# Pressure.net
KiCad netlist of a schematic drawn in EAGLE
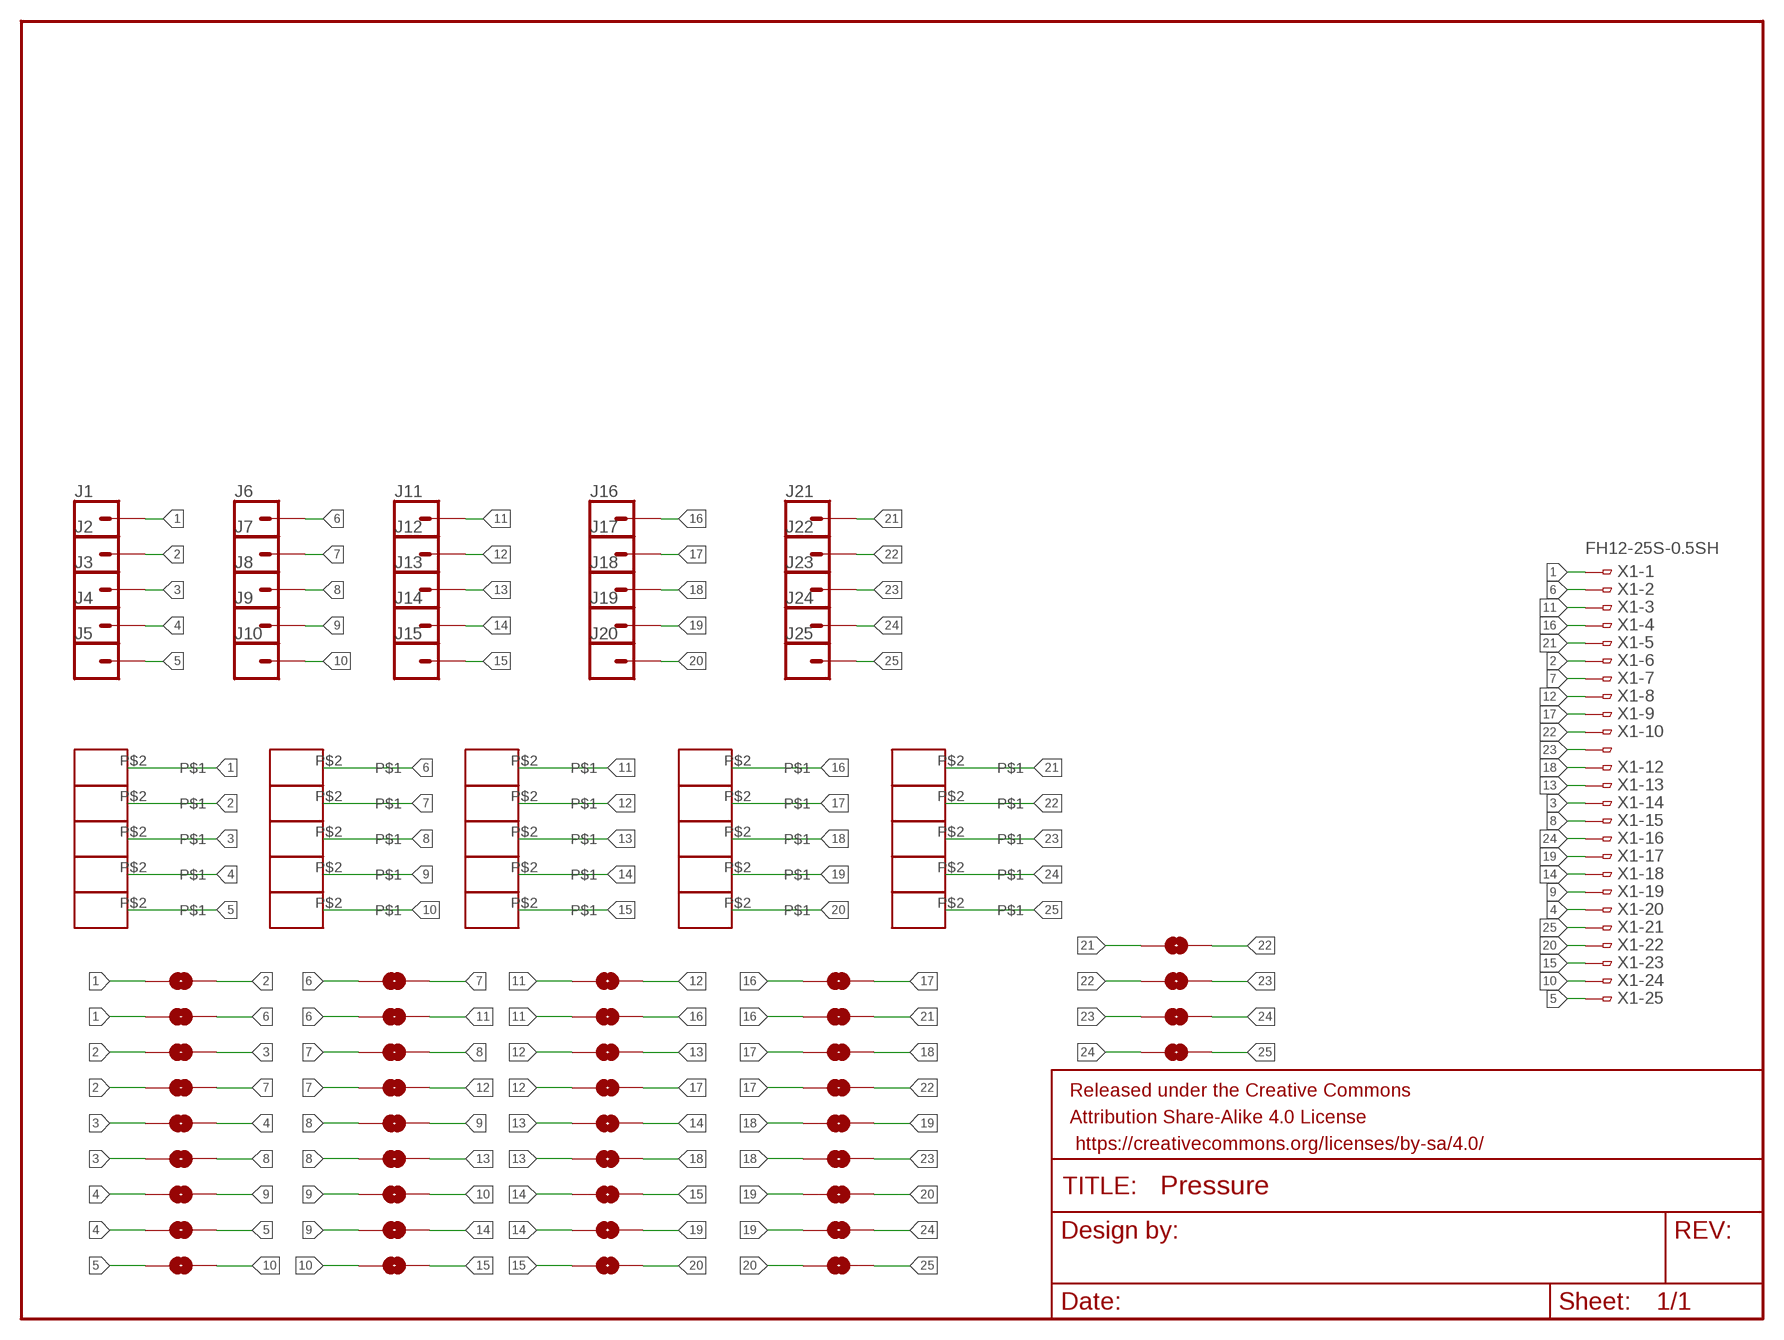
[diagram p0: schematic, sheet 1]

(export (version "E")
  (design (tool "Eeschema 10.0.6"))
  (components
    (comp (ref "FRAME1")
      (value "FRAME-LETTERNO_PACKAGE")
      (footprint "eagle-import:DUMMY")
      (fields (field (name "DESIGNER") "Nobody"))
      (libsource (lib "eagle-import") (part "FRAME-LETTERNO_PACKAGE"))
    )
    (comp (ref "J1")
      (value "CONN_01PTH_NO_SILK_YES_STOP")
      (footprint "eagle-import:1X01_NO_SILK")
      (libsource (lib "eagle-import") (part "CONN_01PTH_NO_SILK_YES_STOP"))
    )
    (comp (ref "J2")
      (value "CONN_01PTH_NO_SILK_YES_STOP")
      (footprint "eagle-import:1X01_NO_SILK")
      (libsource (lib "eagle-import") (part "CONN_01PTH_NO_SILK_YES_STOP"))
    )
    (comp (ref "J3")
      (value "CONN_01PTH_NO_SILK_YES_STOP")
      (footprint "eagle-import:1X01_NO_SILK")
      (libsource (lib "eagle-import") (part "CONN_01PTH_NO_SILK_YES_STOP"))
    )
    (comp (ref "J4")
      (value "CONN_01PTH_NO_SILK_YES_STOP")
      (footprint "eagle-import:1X01_NO_SILK")
      (libsource (lib "eagle-import") (part "CONN_01PTH_NO_SILK_YES_STOP"))
    )
    (comp (ref "J5")
      (value "CONN_01PTH_NO_SILK_YES_STOP")
      (footprint "eagle-import:1X01_NO_SILK")
      (libsource (lib "eagle-import") (part "CONN_01PTH_NO_SILK_YES_STOP"))
    )
    (comp (ref "J6")
      (value "CONN_01PTH_NO_SILK_YES_STOP")
      (footprint "eagle-import:1X01_NO_SILK")
      (libsource (lib "eagle-import") (part "CONN_01PTH_NO_SILK_YES_STOP"))
    )
    (comp (ref "J7")
      (value "CONN_01PTH_NO_SILK_YES_STOP")
      (footprint "eagle-import:1X01_NO_SILK")
      (libsource (lib "eagle-import") (part "CONN_01PTH_NO_SILK_YES_STOP"))
    )
    (comp (ref "J8")
      (value "CONN_01PTH_NO_SILK_YES_STOP")
      (footprint "eagle-import:1X01_NO_SILK")
      (libsource (lib "eagle-import") (part "CONN_01PTH_NO_SILK_YES_STOP"))
    )
    (comp (ref "J9")
      (value "CONN_01PTH_NO_SILK_YES_STOP")
      (footprint "eagle-import:1X01_NO_SILK")
      (libsource (lib "eagle-import") (part "CONN_01PTH_NO_SILK_YES_STOP"))
    )
    (comp (ref "J10")
      (value "CONN_01PTH_NO_SILK_YES_STOP")
      (footprint "eagle-import:1X01_NO_SILK")
      (libsource (lib "eagle-import") (part "CONN_01PTH_NO_SILK_YES_STOP"))
    )
    (comp (ref "J11")
      (value "CONN_01PTH_NO_SILK_YES_STOP")
      (footprint "eagle-import:1X01_NO_SILK")
      (libsource (lib "eagle-import") (part "CONN_01PTH_NO_SILK_YES_STOP"))
    )
    (comp (ref "J12")
      (value "CONN_01PTH_NO_SILK_YES_STOP")
      (footprint "eagle-import:1X01_NO_SILK")
      (libsource (lib "eagle-import") (part "CONN_01PTH_NO_SILK_YES_STOP"))
    )
    (comp (ref "J13")
      (value "CONN_01PTH_NO_SILK_YES_STOP")
      (footprint "eagle-import:1X01_NO_SILK")
      (libsource (lib "eagle-import") (part "CONN_01PTH_NO_SILK_YES_STOP"))
    )
    (comp (ref "J14")
      (value "CONN_01PTH_NO_SILK_YES_STOP")
      (footprint "eagle-import:1X01_NO_SILK")
      (libsource (lib "eagle-import") (part "CONN_01PTH_NO_SILK_YES_STOP"))
    )
    (comp (ref "J15")
      (value "CONN_01PTH_NO_SILK_YES_STOP")
      (footprint "eagle-import:1X01_NO_SILK")
      (libsource (lib "eagle-import") (part "CONN_01PTH_NO_SILK_YES_STOP"))
    )
    (comp (ref "J16")
      (value "CONN_01PTH_NO_SILK_YES_STOP")
      (footprint "eagle-import:1X01_NO_SILK")
      (libsource (lib "eagle-import") (part "CONN_01PTH_NO_SILK_YES_STOP"))
    )
    (comp (ref "J17")
      (value "CONN_01PTH_NO_SILK_YES_STOP")
      (footprint "eagle-import:1X01_NO_SILK")
      (libsource (lib "eagle-import") (part "CONN_01PTH_NO_SILK_YES_STOP"))
    )
    (comp (ref "J18")
      (value "CONN_01PTH_NO_SILK_YES_STOP")
      (footprint "eagle-import:1X01_NO_SILK")
      (libsource (lib "eagle-import") (part "CONN_01PTH_NO_SILK_YES_STOP"))
    )
    (comp (ref "J19")
      (value "CONN_01PTH_NO_SILK_YES_STOP")
      (footprint "eagle-import:1X01_NO_SILK")
      (libsource (lib "eagle-import") (part "CONN_01PTH_NO_SILK_YES_STOP"))
    )
    (comp (ref "J20")
      (value "CONN_01PTH_NO_SILK_YES_STOP")
      (footprint "eagle-import:1X01_NO_SILK")
      (libsource (lib "eagle-import") (part "CONN_01PTH_NO_SILK_YES_STOP"))
    )
    (comp (ref "J21")
      (value "CONN_01PTH_NO_SILK_YES_STOP")
      (footprint "eagle-import:1X01_NO_SILK")
      (libsource (lib "eagle-import") (part "CONN_01PTH_NO_SILK_YES_STOP"))
    )
    (comp (ref "J22")
      (value "CONN_01PTH_NO_SILK_YES_STOP")
      (footprint "eagle-import:1X01_NO_SILK")
      (libsource (lib "eagle-import") (part "CONN_01PTH_NO_SILK_YES_STOP"))
    )
    (comp (ref "J23")
      (value "CONN_01PTH_NO_SILK_YES_STOP")
      (footprint "eagle-import:1X01_NO_SILK")
      (libsource (lib "eagle-import") (part "CONN_01PTH_NO_SILK_YES_STOP"))
    )
    (comp (ref "J24")
      (value "CONN_01PTH_NO_SILK_YES_STOP")
      (footprint "eagle-import:1X01_NO_SILK")
      (libsource (lib "eagle-import") (part "CONN_01PTH_NO_SILK_YES_STOP"))
    )
    (comp (ref "J25")
      (value "CONN_01PTH_NO_SILK_YES_STOP")
      (footprint "eagle-import:1X01_NO_SILK")
      (libsource (lib "eagle-import") (part "CONN_01PTH_NO_SILK_YES_STOP"))
    )
    (comp (ref "JP1")
      (value "JUMPER-SMT_2_NO_NO-SILK")
      (footprint "eagle-import:SMT-JUMPER_2_NO_NO-SILK")
      (libsource (lib "eagle-import") (part "JUMPER-SMT_2_NO_NO-SILK"))
    )
    (comp (ref "JP2")
      (value "JUMPER-SMT_2_NO_NO-SILK")
      (footprint "eagle-import:SMT-JUMPER_2_NO_NO-SILK")
      (libsource (lib "eagle-import") (part "JUMPER-SMT_2_NO_NO-SILK"))
    )
    (comp (ref "JP3")
      (value "JUMPER-SMT_2_NO_NO-SILK")
      (footprint "eagle-import:SMT-JUMPER_2_NO_NO-SILK")
      (libsource (lib "eagle-import") (part "JUMPER-SMT_2_NO_NO-SILK"))
    )
    (comp (ref "JP4")
      (value "JUMPER-SMT_2_NO_NO-SILK")
      (footprint "eagle-import:SMT-JUMPER_2_NO_NO-SILK")
      (libsource (lib "eagle-import") (part "JUMPER-SMT_2_NO_NO-SILK"))
    )
    (comp (ref "JP5")
      (value "JUMPER-SMT_2_NO_NO-SILK")
      (footprint "eagle-import:SMT-JUMPER_2_NO_NO-SILK")
      (libsource (lib "eagle-import") (part "JUMPER-SMT_2_NO_NO-SILK"))
    )
    (comp (ref "JP6")
      (value "JUMPER-SMT_2_NO_NO-SILK")
      (footprint "eagle-import:SMT-JUMPER_2_NO_NO-SILK")
      (libsource (lib "eagle-import") (part "JUMPER-SMT_2_NO_NO-SILK"))
    )
    (comp (ref "JP7")
      (value "JUMPER-SMT_2_NO_NO-SILK")
      (footprint "eagle-import:SMT-JUMPER_2_NO_NO-SILK")
      (libsource (lib "eagle-import") (part "JUMPER-SMT_2_NO_NO-SILK"))
    )
    (comp (ref "JP8")
      (value "JUMPER-SMT_2_NO_NO-SILK")
      (footprint "eagle-import:SMT-JUMPER_2_NO_NO-SILK")
      (libsource (lib "eagle-import") (part "JUMPER-SMT_2_NO_NO-SILK"))
    )
    (comp (ref "JP9")
      (value "JUMPER-SMT_2_NO_NO-SILK")
      (footprint "eagle-import:SMT-JUMPER_2_NO_NO-SILK")
      (libsource (lib "eagle-import") (part "JUMPER-SMT_2_NO_NO-SILK"))
    )
    (comp (ref "JP10")
      (value "JUMPER-SMT_2_NO_NO-SILK")
      (footprint "eagle-import:SMT-JUMPER_2_NO_NO-SILK")
      (libsource (lib "eagle-import") (part "JUMPER-SMT_2_NO_NO-SILK"))
    )
    (comp (ref "JP11")
      (value "JUMPER-SMT_2_NO_NO-SILK")
      (footprint "eagle-import:SMT-JUMPER_2_NO_NO-SILK")
      (libsource (lib "eagle-import") (part "JUMPER-SMT_2_NO_NO-SILK"))
    )
    (comp (ref "JP12")
      (value "JUMPER-SMT_2_NO_NO-SILK")
      (footprint "eagle-import:SMT-JUMPER_2_NO_NO-SILK")
      (libsource (lib "eagle-import") (part "JUMPER-SMT_2_NO_NO-SILK"))
    )
    (comp (ref "JP13")
      (value "JUMPER-SMT_2_NO_NO-SILK")
      (footprint "eagle-import:SMT-JUMPER_2_NO_NO-SILK")
      (libsource (lib "eagle-import") (part "JUMPER-SMT_2_NO_NO-SILK"))
    )
    (comp (ref "JP14")
      (value "JUMPER-SMT_2_NO_NO-SILK")
      (footprint "eagle-import:SMT-JUMPER_2_NO_NO-SILK")
      (libsource (lib "eagle-import") (part "JUMPER-SMT_2_NO_NO-SILK"))
    )
    (comp (ref "JP15")
      (value "JUMPER-SMT_2_NO_NO-SILK")
      (footprint "eagle-import:SMT-JUMPER_2_NO_NO-SILK")
      (libsource (lib "eagle-import") (part "JUMPER-SMT_2_NO_NO-SILK"))
    )
    (comp (ref "JP16")
      (value "JUMPER-SMT_2_NO_NO-SILK")
      (footprint "eagle-import:SMT-JUMPER_2_NO_NO-SILK")
      (libsource (lib "eagle-import") (part "JUMPER-SMT_2_NO_NO-SILK"))
    )
    (comp (ref "JP17")
      (value "JUMPER-SMT_2_NO_NO-SILK")
      (footprint "eagle-import:SMT-JUMPER_2_NO_NO-SILK")
      (libsource (lib "eagle-import") (part "JUMPER-SMT_2_NO_NO-SILK"))
    )
    (comp (ref "JP18")
      (value "JUMPER-SMT_2_NO_NO-SILK")
      (footprint "eagle-import:SMT-JUMPER_2_NO_NO-SILK")
      (libsource (lib "eagle-import") (part "JUMPER-SMT_2_NO_NO-SILK"))
    )
    (comp (ref "JP19")
      (value "JUMPER-SMT_2_NO_NO-SILK")
      (footprint "eagle-import:SMT-JUMPER_2_NO_NO-SILK")
      (libsource (lib "eagle-import") (part "JUMPER-SMT_2_NO_NO-SILK"))
    )
    (comp (ref "JP20")
      (value "JUMPER-SMT_2_NO_NO-SILK")
      (footprint "eagle-import:SMT-JUMPER_2_NO_NO-SILK")
      (libsource (lib "eagle-import") (part "JUMPER-SMT_2_NO_NO-SILK"))
    )
    (comp (ref "JP21")
      (value "JUMPER-SMT_2_NO_NO-SILK")
      (footprint "eagle-import:SMT-JUMPER_2_NO_NO-SILK")
      (libsource (lib "eagle-import") (part "JUMPER-SMT_2_NO_NO-SILK"))
    )
    (comp (ref "JP22")
      (value "JUMPER-SMT_2_NO_NO-SILK")
      (footprint "eagle-import:SMT-JUMPER_2_NO_NO-SILK")
      (libsource (lib "eagle-import") (part "JUMPER-SMT_2_NO_NO-SILK"))
    )
    (comp (ref "JP23")
      (value "JUMPER-SMT_2_NO_NO-SILK")
      (footprint "eagle-import:SMT-JUMPER_2_NO_NO-SILK")
      (libsource (lib "eagle-import") (part "JUMPER-SMT_2_NO_NO-SILK"))
    )
    (comp (ref "JP24")
      (value "JUMPER-SMT_2_NO_NO-SILK")
      (footprint "eagle-import:SMT-JUMPER_2_NO_NO-SILK")
      (libsource (lib "eagle-import") (part "JUMPER-SMT_2_NO_NO-SILK"))
    )
    (comp (ref "JP25")
      (value "JUMPER-SMT_2_NO_NO-SILK")
      (footprint "eagle-import:SMT-JUMPER_2_NO_NO-SILK")
      (libsource (lib "eagle-import") (part "JUMPER-SMT_2_NO_NO-SILK"))
    )
    (comp (ref "JP26")
      (value "JUMPER-SMT_2_NO_NO-SILK")
      (footprint "eagle-import:SMT-JUMPER_2_NO_NO-SILK")
      (libsource (lib "eagle-import") (part "JUMPER-SMT_2_NO_NO-SILK"))
    )
    (comp (ref "JP27")
      (value "JUMPER-SMT_2_NO_NO-SILK")
      (footprint "eagle-import:SMT-JUMPER_2_NO_NO-SILK")
      (libsource (lib "eagle-import") (part "JUMPER-SMT_2_NO_NO-SILK"))
    )
    (comp (ref "JP28")
      (value "JUMPER-SMT_2_NO_NO-SILK")
      (footprint "eagle-import:SMT-JUMPER_2_NO_NO-SILK")
      (libsource (lib "eagle-import") (part "JUMPER-SMT_2_NO_NO-SILK"))
    )
    (comp (ref "JP29")
      (value "JUMPER-SMT_2_NO_NO-SILK")
      (footprint "eagle-import:SMT-JUMPER_2_NO_NO-SILK")
      (libsource (lib "eagle-import") (part "JUMPER-SMT_2_NO_NO-SILK"))
    )
    (comp (ref "JP30")
      (value "JUMPER-SMT_2_NO_NO-SILK")
      (footprint "eagle-import:SMT-JUMPER_2_NO_NO-SILK")
      (libsource (lib "eagle-import") (part "JUMPER-SMT_2_NO_NO-SILK"))
    )
    (comp (ref "JP31")
      (value "JUMPER-SMT_2_NO_NO-SILK")
      (footprint "eagle-import:SMT-JUMPER_2_NO_NO-SILK")
      (libsource (lib "eagle-import") (part "JUMPER-SMT_2_NO_NO-SILK"))
    )
    (comp (ref "JP32")
      (value "JUMPER-SMT_2_NO_NO-SILK")
      (footprint "eagle-import:SMT-JUMPER_2_NO_NO-SILK")
      (libsource (lib "eagle-import") (part "JUMPER-SMT_2_NO_NO-SILK"))
    )
    (comp (ref "JP33")
      (value "JUMPER-SMT_2_NO_NO-SILK")
      (footprint "eagle-import:SMT-JUMPER_2_NO_NO-SILK")
      (libsource (lib "eagle-import") (part "JUMPER-SMT_2_NO_NO-SILK"))
    )
    (comp (ref "JP34")
      (value "JUMPER-SMT_2_NO_NO-SILK")
      (footprint "eagle-import:SMT-JUMPER_2_NO_NO-SILK")
      (libsource (lib "eagle-import") (part "JUMPER-SMT_2_NO_NO-SILK"))
    )
    (comp (ref "JP35")
      (value "JUMPER-SMT_2_NO_NO-SILK")
      (footprint "eagle-import:SMT-JUMPER_2_NO_NO-SILK")
      (libsource (lib "eagle-import") (part "JUMPER-SMT_2_NO_NO-SILK"))
    )
    (comp (ref "JP36")
      (value "JUMPER-SMT_2_NO_NO-SILK")
      (footprint "eagle-import:SMT-JUMPER_2_NO_NO-SILK")
      (libsource (lib "eagle-import") (part "JUMPER-SMT_2_NO_NO-SILK"))
    )
    (comp (ref "JP37")
      (value "JUMPER-SMT_2_NO_NO-SILK")
      (footprint "eagle-import:SMT-JUMPER_2_NO_NO-SILK")
      (libsource (lib "eagle-import") (part "JUMPER-SMT_2_NO_NO-SILK"))
    )
    (comp (ref "JP38")
      (value "JUMPER-SMT_2_NO_NO-SILK")
      (footprint "eagle-import:SMT-JUMPER_2_NO_NO-SILK")
      (libsource (lib "eagle-import") (part "JUMPER-SMT_2_NO_NO-SILK"))
    )
    (comp (ref "JP39")
      (value "JUMPER-SMT_2_NO_NO-SILK")
      (footprint "eagle-import:SMT-JUMPER_2_NO_NO-SILK")
      (libsource (lib "eagle-import") (part "JUMPER-SMT_2_NO_NO-SILK"))
    )
    (comp (ref "JP40")
      (value "JUMPER-SMT_2_NO_NO-SILK")
      (footprint "eagle-import:SMT-JUMPER_2_NO_NO-SILK")
      (libsource (lib "eagle-import") (part "JUMPER-SMT_2_NO_NO-SILK"))
    )
    (comp (ref "U$1")
      (value "250MIL_1X1")
      (footprint "eagle-import:250MIL_1X1")
      (libsource (lib "eagle-import") (part "250MIL_1X1"))
    )
    (comp (ref "U$2")
      (value "250MIL_1X1")
      (footprint "eagle-import:250MIL_1X1")
      (libsource (lib "eagle-import") (part "250MIL_1X1"))
    )
    (comp (ref "U$3")
      (value "250MIL_1X1")
      (footprint "eagle-import:250MIL_1X1")
      (libsource (lib "eagle-import") (part "250MIL_1X1"))
    )
    (comp (ref "U$4")
      (value "250MIL_1X1")
      (footprint "eagle-import:250MIL_1X1")
      (libsource (lib "eagle-import") (part "250MIL_1X1"))
    )
    (comp (ref "U$5")
      (value "250MIL_1X1")
      (footprint "eagle-import:250MIL_1X1")
      (libsource (lib "eagle-import") (part "250MIL_1X1"))
    )
    (comp (ref "U$6")
      (value "250MIL_1X1")
      (footprint "eagle-import:250MIL_1X1")
      (libsource (lib "eagle-import") (part "250MIL_1X1"))
    )
    (comp (ref "U$7")
      (value "250MIL_1X1")
      (footprint "eagle-import:250MIL_1X1")
      (libsource (lib "eagle-import") (part "250MIL_1X1"))
    )
    (comp (ref "U$8")
      (value "250MIL_1X1")
      (footprint "eagle-import:250MIL_1X1")
      (libsource (lib "eagle-import") (part "250MIL_1X1"))
    )
    (comp (ref "U$9")
      (value "250MIL_1X1")
      (footprint "eagle-import:250MIL_1X1")
      (libsource (lib "eagle-import") (part "250MIL_1X1"))
    )
    (comp (ref "U$10")
      (value "250MIL_1X1")
      (footprint "eagle-import:250MIL_1X1")
      (libsource (lib "eagle-import") (part "250MIL_1X1"))
    )
    (comp (ref "U$11")
      (value "250MIL_1X1")
      (footprint "eagle-import:250MIL_1X1")
      (libsource (lib "eagle-import") (part "250MIL_1X1"))
    )
    (comp (ref "U$12")
      (value "250MIL_1X1")
      (footprint "eagle-import:250MIL_1X1")
      (libsource (lib "eagle-import") (part "250MIL_1X1"))
    )
    (comp (ref "U$13")
      (value "250MIL_1X1")
      (footprint "eagle-import:250MIL_1X1")
      (libsource (lib "eagle-import") (part "250MIL_1X1"))
    )
    (comp (ref "U$14")
      (value "250MIL_1X1")
      (footprint "eagle-import:250MIL_1X1")
      (libsource (lib "eagle-import") (part "250MIL_1X1"))
    )
    (comp (ref "U$15")
      (value "250MIL_1X1")
      (footprint "eagle-import:250MIL_1X1")
      (libsource (lib "eagle-import") (part "250MIL_1X1"))
    )
    (comp (ref "U$16")
      (value "250MIL_1X1")
      (footprint "eagle-import:250MIL_1X1")
      (libsource (lib "eagle-import") (part "250MIL_1X1"))
    )
    (comp (ref "U$17")
      (value "250MIL_1X1")
      (footprint "eagle-import:250MIL_1X1")
      (libsource (lib "eagle-import") (part "250MIL_1X1"))
    )
    (comp (ref "U$18")
      (value "250MIL_1X1")
      (footprint "eagle-import:250MIL_1X1")
      (libsource (lib "eagle-import") (part "250MIL_1X1"))
    )
    (comp (ref "U$19")
      (value "250MIL_1X1")
      (footprint "eagle-import:250MIL_1X1")
      (libsource (lib "eagle-import") (part "250MIL_1X1"))
    )
    (comp (ref "U$20")
      (value "250MIL_1X1")
      (footprint "eagle-import:250MIL_1X1")
      (libsource (lib "eagle-import") (part "250MIL_1X1"))
    )
    (comp (ref "U$21")
      (value "250MIL_1X1")
      (footprint "eagle-import:250MIL_1X1")
      (libsource (lib "eagle-import") (part "250MIL_1X1"))
    )
    (comp (ref "U$22")
      (value "250MIL_1X1")
      (footprint "eagle-import:250MIL_1X1")
      (libsource (lib "eagle-import") (part "250MIL_1X1"))
    )
    (comp (ref "U$23")
      (value "250MIL_1X1")
      (footprint "eagle-import:250MIL_1X1")
      (libsource (lib "eagle-import") (part "250MIL_1X1"))
    )
    (comp (ref "U$24")
      (value "250MIL_1X1")
      (footprint "eagle-import:250MIL_1X1")
      (libsource (lib "eagle-import") (part "250MIL_1X1"))
    )
    (comp (ref "U$25")
      (value "250MIL_1X1")
      (footprint "eagle-import:250MIL_1X1")
      (libsource (lib "eagle-import") (part "250MIL_1X1"))
    )
    (comp (ref "X1")
      (value "FH12-25S-0.5SH")
      (footprint "eagle-import:FH12-25S-0.5SH")
      (libsource (lib "eagle-import") (part "FH12-25S-0.5SH"))
    )
  )
  (nets
    (net (code "1") (name "1") (class "Default")
      (node (ref "J1") (pin "1") (pinfunction "1_1") (pintype "passive"))
      (node (ref "JP1") (pin "1") (pinfunction "1_1") (pintype "passive"))
      (node (ref "JP2") (pin "1") (pinfunction "1_1") (pintype "passive"))
      (node (ref "U$1") (pin "P$2") (pinfunction "P$1_P$2") (pintype "bidirectional"))
      (node (ref "X1") (pin "1") (pinfunction "1_1") (pintype "passive"))
    )
    (net (code "2") (name "2") (class "Default")
      (node (ref "J2") (pin "1") (pinfunction "1_1") (pintype "passive"))
      (node (ref "JP1") (pin "2") (pinfunction "2_2") (pintype "passive"))
      (node (ref "JP3") (pin "1") (pinfunction "1_1") (pintype "passive"))
      (node (ref "JP4") (pin "1") (pinfunction "1_1") (pintype "passive"))
      (node (ref "U$2") (pin "P$2") (pinfunction "P$1_P$2") (pintype "bidirectional"))
      (node (ref "X1") (pin "6") (pinfunction "1_6") (pintype "passive"))
    )
    (net (code "3") (name "3") (class "Default")
      (node (ref "J3") (pin "1") (pinfunction "1_1") (pintype "passive"))
      (node (ref "JP3") (pin "2") (pinfunction "2_2") (pintype "passive"))
      (node (ref "JP5") (pin "1") (pinfunction "1_1") (pintype "passive"))
      (node (ref "JP6") (pin "1") (pinfunction "1_1") (pintype "passive"))
      (node (ref "U$3") (pin "P$2") (pinfunction "P$1_P$2") (pintype "bidirectional"))
      (node (ref "X1") (pin "14") (pinfunction "1_14") (pintype "passive"))
    )
    (net (code "4") (name "4") (class "Default")
      (node (ref "J4") (pin "1") (pinfunction "1_1") (pintype "passive"))
      (node (ref "JP5") (pin "2") (pinfunction "2_2") (pintype "passive"))
      (node (ref "JP7") (pin "1") (pinfunction "1_1") (pintype "passive"))
      (node (ref "JP8") (pin "1") (pinfunction "1_1") (pintype "passive"))
      (node (ref "U$4") (pin "P$2") (pinfunction "P$1_P$2") (pintype "bidirectional"))
      (node (ref "X1") (pin "20") (pinfunction "1_20") (pintype "passive"))
    )
    (net (code "5") (name "5") (class "Default")
      (node (ref "J5") (pin "1") (pinfunction "1_1") (pintype "passive"))
      (node (ref "JP8") (pin "2") (pinfunction "2_2") (pintype "passive"))
      (node (ref "JP9") (pin "1") (pinfunction "1_1") (pintype "passive"))
      (node (ref "U$5") (pin "P$2") (pinfunction "P$1_P$2") (pintype "bidirectional"))
      (node (ref "X1") (pin "25") (pinfunction "1_25") (pintype "passive"))
    )
    (net (code "6") (name "6") (class "Default")
      (node (ref "J6") (pin "1") (pinfunction "1_1") (pintype "passive"))
      (node (ref "JP10") (pin "1") (pinfunction "1_1") (pintype "passive"))
      (node (ref "JP11") (pin "1") (pinfunction "1_1") (pintype "passive"))
      (node (ref "JP2") (pin "2") (pinfunction "2_2") (pintype "passive"))
      (node (ref "U$6") (pin "P$2") (pinfunction "P$1_P$2") (pintype "bidirectional"))
      (node (ref "X1") (pin "2") (pinfunction "1_2") (pintype "passive"))
    )
    (net (code "7") (name "7") (class "Default")
      (node (ref "J7") (pin "1") (pinfunction "1_1") (pintype "passive"))
      (node (ref "JP10") (pin "2") (pinfunction "2_2") (pintype "passive"))
      (node (ref "JP12") (pin "1") (pinfunction "1_1") (pintype "passive"))
      (node (ref "JP13") (pin "1") (pinfunction "1_1") (pintype "passive"))
      (node (ref "JP4") (pin "2") (pinfunction "2_2") (pintype "passive"))
      (node (ref "U$7") (pin "P$2") (pinfunction "P$1_P$2") (pintype "bidirectional"))
      (node (ref "X1") (pin "7") (pinfunction "1_7") (pintype "passive"))
    )
    (net (code "8") (name "8") (class "Default")
      (node (ref "J8") (pin "1") (pinfunction "1_1") (pintype "passive"))
      (node (ref "JP12") (pin "2") (pinfunction "2_2") (pintype "passive"))
      (node (ref "JP14") (pin "1") (pinfunction "1_1") (pintype "passive"))
      (node (ref "JP15") (pin "1") (pinfunction "1_1") (pintype "passive"))
      (node (ref "JP6") (pin "2") (pinfunction "2_2") (pintype "passive"))
      (node (ref "U$8") (pin "P$2") (pinfunction "P$1_P$2") (pintype "bidirectional"))
      (node (ref "X1") (pin "15") (pinfunction "1_15") (pintype "passive"))
    )
    (net (code "9") (name "9") (class "Default")
      (node (ref "J9") (pin "1") (pinfunction "1_1") (pintype "passive"))
      (node (ref "JP14") (pin "2") (pinfunction "2_2") (pintype "passive"))
      (node (ref "JP16") (pin "1") (pinfunction "1_1") (pintype "passive"))
      (node (ref "JP17") (pin "1") (pinfunction "1_1") (pintype "passive"))
      (node (ref "JP7") (pin "2") (pinfunction "2_2") (pintype "passive"))
      (node (ref "U$9") (pin "P$2") (pinfunction "P$1_P$2") (pintype "bidirectional"))
      (node (ref "X1") (pin "19") (pinfunction "1_19") (pintype "passive"))
    )
    (net (code "10") (name "10") (class "Default")
      (node (ref "J10") (pin "1") (pinfunction "1_1") (pintype "passive"))
      (node (ref "JP16") (pin "2") (pinfunction "2_2") (pintype "passive"))
      (node (ref "JP18") (pin "1") (pinfunction "1_1") (pintype "passive"))
      (node (ref "JP9") (pin "2") (pinfunction "2_2") (pintype "passive"))
      (node (ref "U$10") (pin "P$2") (pinfunction "P$1_P$2") (pintype "bidirectional"))
      (node (ref "X1") (pin "24") (pinfunction "1_24") (pintype "passive"))
    )
    (net (code "11") (name "11") (class "Default")
      (node (ref "J11") (pin "1") (pinfunction "1_1") (pintype "passive"))
      (node (ref "JP11") (pin "2") (pinfunction "2_2") (pintype "passive"))
      (node (ref "JP19") (pin "1") (pinfunction "1_1") (pintype "passive"))
      (node (ref "JP20") (pin "1") (pinfunction "1_1") (pintype "passive"))
      (node (ref "U$11") (pin "P$2") (pinfunction "P$1_P$2") (pintype "bidirectional"))
      (node (ref "X1") (pin "3") (pinfunction "1_3") (pintype "passive"))
    )
    (net (code "12") (name "12") (class "Default")
      (node (ref "J12") (pin "1") (pinfunction "1_1") (pintype "passive"))
      (node (ref "JP13") (pin "2") (pinfunction "2_2") (pintype "passive"))
      (node (ref "JP19") (pin "2") (pinfunction "2_2") (pintype "passive"))
      (node (ref "JP21") (pin "1") (pinfunction "1_1") (pintype "passive"))
      (node (ref "JP22") (pin "1") (pinfunction "1_1") (pintype "passive"))
      (node (ref "U$12") (pin "P$2") (pinfunction "P$1_P$2") (pintype "bidirectional"))
      (node (ref "X1") (pin "8") (pinfunction "1_8") (pintype "passive"))
    )
    (net (code "13") (name "13") (class "Default")
      (node (ref "J13") (pin "1") (pinfunction "1_1") (pintype "passive"))
      (node (ref "JP15") (pin "2") (pinfunction "2_2") (pintype "passive"))
      (node (ref "JP21") (pin "2") (pinfunction "2_2") (pintype "passive"))
      (node (ref "JP23") (pin "1") (pinfunction "1_1") (pintype "passive"))
      (node (ref "JP24") (pin "1") (pinfunction "1_1") (pintype "passive"))
      (node (ref "U$13") (pin "P$2") (pinfunction "P$1_P$2") (pintype "bidirectional"))
      (node (ref "X1") (pin "13") (pinfunction "1_13") (pintype "passive"))
    )
    (net (code "14") (name "14") (class "Default")
      (node (ref "J14") (pin "1") (pinfunction "1_1") (pintype "passive"))
      (node (ref "JP17") (pin "2") (pinfunction "2_2") (pintype "passive"))
      (node (ref "JP23") (pin "2") (pinfunction "2_2") (pintype "passive"))
      (node (ref "JP25") (pin "1") (pinfunction "1_1") (pintype "passive"))
      (node (ref "JP26") (pin "1") (pinfunction "1_1") (pintype "passive"))
      (node (ref "U$14") (pin "P$2") (pinfunction "P$1_P$2") (pintype "bidirectional"))
      (node (ref "X1") (pin "18") (pinfunction "1_18") (pintype "passive"))
    )
    (net (code "15") (name "15") (class "Default")
      (node (ref "J15") (pin "1") (pinfunction "1_1") (pintype "passive"))
      (node (ref "JP18") (pin "2") (pinfunction "2_2") (pintype "passive"))
      (node (ref "JP25") (pin "2") (pinfunction "2_2") (pintype "passive"))
      (node (ref "JP27") (pin "1") (pinfunction "1_1") (pintype "passive"))
      (node (ref "U$15") (pin "P$2") (pinfunction "P$1_P$2") (pintype "bidirectional"))
      (node (ref "X1") (pin "23") (pinfunction "1_23") (pintype "passive"))
    )
    (net (code "16") (name "16") (class "Default")
      (node (ref "J16") (pin "1") (pinfunction "1_1") (pintype "passive"))
      (node (ref "JP20") (pin "2") (pinfunction "2_2") (pintype "passive"))
      (node (ref "JP28") (pin "1") (pinfunction "1_1") (pintype "passive"))
      (node (ref "JP29") (pin "1") (pinfunction "1_1") (pintype "passive"))
      (node (ref "U$16") (pin "P$2") (pinfunction "P$1_P$2") (pintype "bidirectional"))
      (node (ref "X1") (pin "4") (pinfunction "1_4") (pintype "passive"))
    )
    (net (code "17") (name "17") (class "Default")
      (node (ref "J17") (pin "1") (pinfunction "1_1") (pintype "passive"))
      (node (ref "JP22") (pin "2") (pinfunction "2_2") (pintype "passive"))
      (node (ref "JP28") (pin "2") (pinfunction "2_2") (pintype "passive"))
      (node (ref "JP30") (pin "1") (pinfunction "1_1") (pintype "passive"))
      (node (ref "JP31") (pin "1") (pinfunction "1_1") (pintype "passive"))
      (node (ref "U$17") (pin "P$2") (pinfunction "P$1_P$2") (pintype "bidirectional"))
      (node (ref "X1") (pin "9") (pinfunction "1_9") (pintype "passive"))
    )
    (net (code "18") (name "18") (class "Default")
      (node (ref "J18") (pin "1") (pinfunction "1_1") (pintype "passive"))
      (node (ref "JP24") (pin "2") (pinfunction "2_2") (pintype "passive"))
      (node (ref "JP30") (pin "2") (pinfunction "2_2") (pintype "passive"))
      (node (ref "JP32") (pin "1") (pinfunction "1_1") (pintype "passive"))
      (node (ref "JP33") (pin "1") (pinfunction "1_1") (pintype "passive"))
      (node (ref "U$18") (pin "P$2") (pinfunction "P$1_P$2") (pintype "bidirectional"))
      (node (ref "X1") (pin "12") (pinfunction "1_12") (pintype "passive"))
    )
    (net (code "19") (name "19") (class "Default")
      (node (ref "J19") (pin "1") (pinfunction "1_1") (pintype "passive"))
      (node (ref "JP26") (pin "2") (pinfunction "2_2") (pintype "passive"))
      (node (ref "JP32") (pin "2") (pinfunction "2_2") (pintype "passive"))
      (node (ref "JP34") (pin "1") (pinfunction "1_1") (pintype "passive"))
      (node (ref "JP35") (pin "1") (pinfunction "1_1") (pintype "passive"))
      (node (ref "U$19") (pin "P$2") (pinfunction "P$1_P$2") (pintype "bidirectional"))
      (node (ref "X1") (pin "17") (pinfunction "1_17") (pintype "passive"))
    )
    (net (code "20") (name "20") (class "Default")
      (node (ref "J20") (pin "1") (pinfunction "1_1") (pintype "passive"))
      (node (ref "JP27") (pin "2") (pinfunction "2_2") (pintype "passive"))
      (node (ref "JP34") (pin "2") (pinfunction "2_2") (pintype "passive"))
      (node (ref "JP36") (pin "1") (pinfunction "1_1") (pintype "passive"))
      (node (ref "U$20") (pin "P$2") (pinfunction "P$1_P$2") (pintype "bidirectional"))
      (node (ref "X1") (pin "22") (pinfunction "1_22") (pintype "passive"))
    )
    (net (code "21") (name "21") (class "Default")
      (node (ref "J21") (pin "1") (pinfunction "1_1") (pintype "passive"))
      (node (ref "JP29") (pin "2") (pinfunction "2_2") (pintype "passive"))
      (node (ref "JP37") (pin "1") (pinfunction "1_1") (pintype "passive"))
      (node (ref "U$21") (pin "P$2") (pinfunction "P$1_P$2") (pintype "bidirectional"))
      (node (ref "X1") (pin "5") (pinfunction "1_5") (pintype "passive"))
    )
    (net (code "22") (name "22") (class "Default")
      (node (ref "J22") (pin "1") (pinfunction "1_1") (pintype "passive"))
      (node (ref "JP31") (pin "2") (pinfunction "2_2") (pintype "passive"))
      (node (ref "JP37") (pin "2") (pinfunction "2_2") (pintype "passive"))
      (node (ref "JP38") (pin "1") (pinfunction "1_1") (pintype "passive"))
      (node (ref "U$22") (pin "P$2") (pinfunction "P$1_P$2") (pintype "bidirectional"))
      (node (ref "X1") (pin "10") (pinfunction "1_10") (pintype "passive"))
    )
    (net (code "23") (name "23") (class "Default")
      (node (ref "J23") (pin "1") (pinfunction "1_1") (pintype "passive"))
      (node (ref "JP33") (pin "2") (pinfunction "2_2") (pintype "passive"))
      (node (ref "JP38") (pin "2") (pinfunction "2_2") (pintype "passive"))
      (node (ref "JP39") (pin "1") (pinfunction "1_1") (pintype "passive"))
      (node (ref "U$23") (pin "P$2") (pinfunction "P$1_P$2") (pintype "bidirectional"))
      (node (ref "X1") (pin "11") (pinfunction "1_11") (pintype "passive"))
    )
    (net (code "24") (name "24") (class "Default")
      (node (ref "J24") (pin "1") (pinfunction "1_1") (pintype "passive"))
      (node (ref "JP35") (pin "2") (pinfunction "2_2") (pintype "passive"))
      (node (ref "JP39") (pin "2") (pinfunction "2_2") (pintype "passive"))
      (node (ref "JP40") (pin "1") (pinfunction "1_1") (pintype "passive"))
      (node (ref "U$24") (pin "P$2") (pinfunction "P$1_P$2") (pintype "bidirectional"))
      (node (ref "X1") (pin "16") (pinfunction "1_16") (pintype "passive"))
    )
    (net (code "25") (name "25") (class "Default")
      (node (ref "J25") (pin "1") (pinfunction "1_1") (pintype "passive"))
      (node (ref "JP36") (pin "2") (pinfunction "2_2") (pintype "passive"))
      (node (ref "JP40") (pin "2") (pinfunction "2_2") (pintype "passive"))
      (node (ref "U$25") (pin "P$2") (pinfunction "P$1_P$2") (pintype "bidirectional"))
      (node (ref "X1") (pin "21") (pinfunction "1_21") (pintype "passive"))
    )
  )
)
